# Aq1B_Guppy.net
KiCad netlist of a schematic drawn in Altium Designer
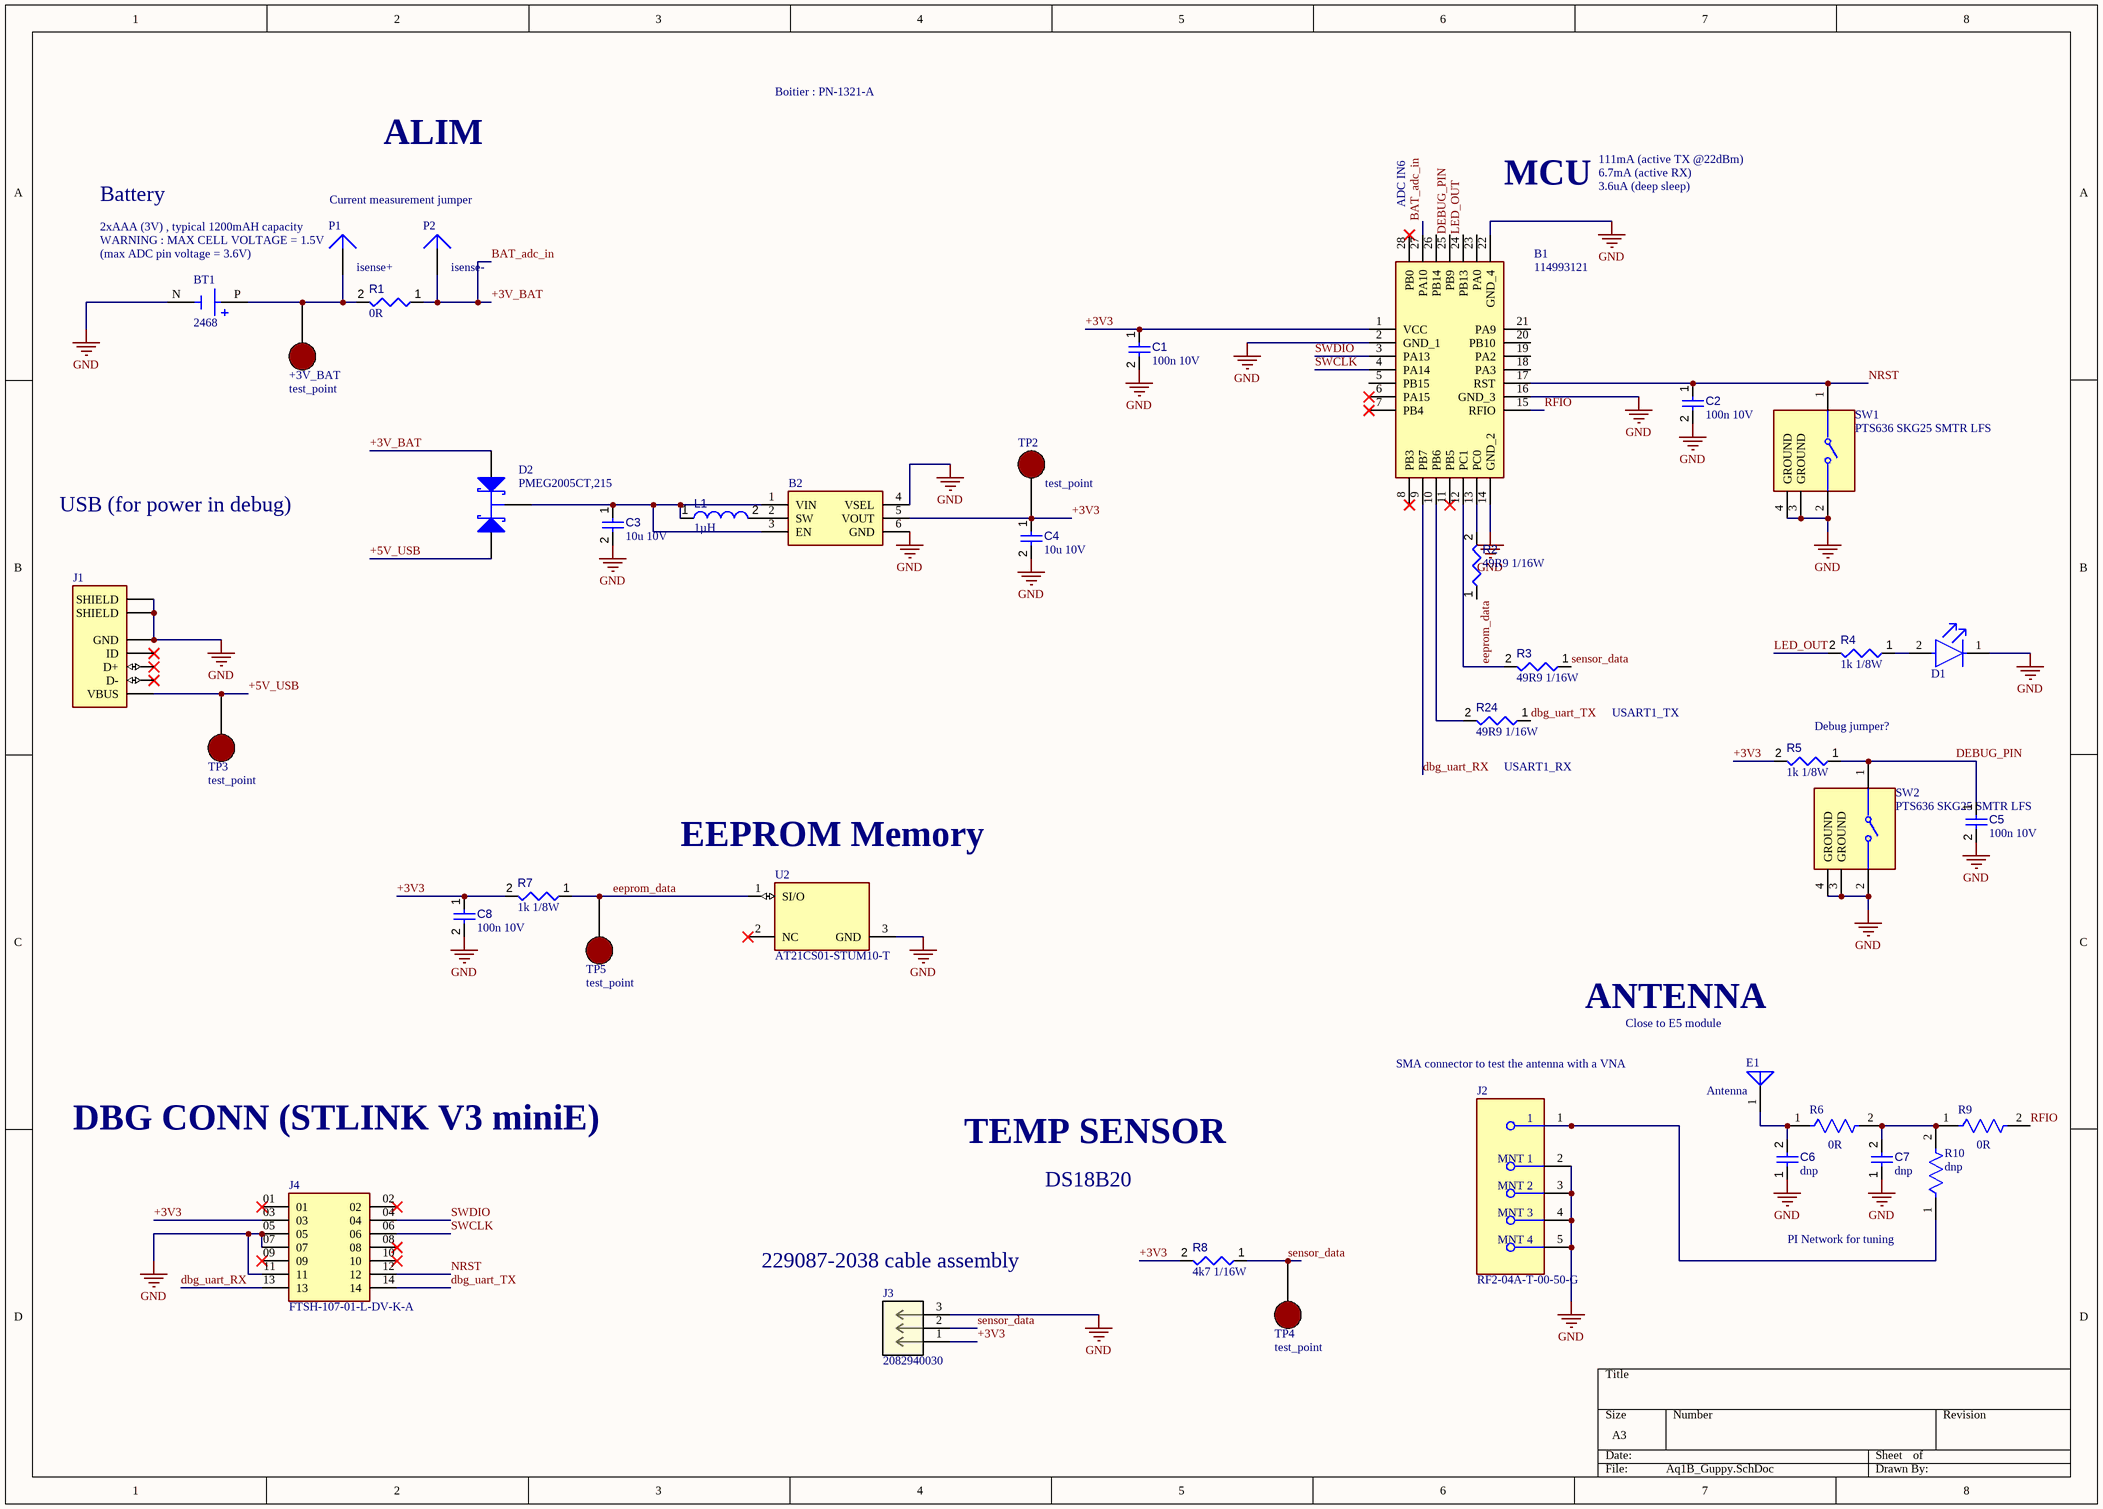
[diagram p0: Aq1B_Guppy.SchDoc]

(export (version "E")
  (design (tool "Eeschema 10.0.6"))
  (components
    (comp (ref "+3V_BAT")
      (value "test_point")
      (footprint "test_point")
      (libsource (lib "test_point") (part "test_point"))
    )
    (comp (ref "B1")
      (value "114993121")
      (footprint "114993121")
      (description "General ISM < 1GHz LoRaWAN Transceiver Module 868MHz, 915MHz Antenna Not Included Surface Mount")
      (fields (field (name "MOUSER PART NUMBER") "713-114993121"))
      (libsource (lib "LoraE5") (part "114993121"))
    )
    (comp (ref "B2")
      (value "~")
      (footprint "SOTFL50P160X60-6N")
      (fields
        (field (name "MOUSER PART NUMBER") "595-TPS61299DRLR")
        (field (name "MANUFACTURER_PART_NUMBER") "TPS61299DRLR")
      )
      (libsource (lib "AqOST_Guppy") (part "TPS61299DRLR"))
    )
    (comp (ref "BT1")
      (value "2468")
      (footprint "BAT_2468")
      (description "Battery Holder, THM, 2 Cell, Cell Size AAA, Plastic ¦ Keystone Electronics 2468")
      (fields (field (name "MF") "Keystone Electronics"))
      (libsource (lib "2468") (part "2468"))
    )
    (comp (ref "C1")
      (value "100n 10V")
      (footprint "CAPC0805(2012)145_L")
      (description "Chip Capacitor, 4.7µF +/-40%, 25V, 0805, Thickness 1.45 mm")
      (fields (field (name "TOLERANCE") "20%") (field (name "Comment") "Capacitor 4.7µF +/-40% 25V 0805"))
      (libsource (lib "Samuel Grall") (part "CAP-NP-2"))
    )
    (comp (ref "C2")
      (value "100n 10V")
      (footprint "CAPC0805(2012)145_L")
      (description "Chip Capacitor, 4.7µF +/-40%, 25V, 0805, Thickness 1.45 mm")
      (fields (field (name "TOLERANCE") "20%") (field (name "Comment") "Capacitor 4.7µF +/-40% 25V 0805"))
      (libsource (lib "Samuel Grall") (part "CAP-NP-2"))
    )
    (comp (ref "C3")
      (value "10u 10V")
      (footprint "CAPC0805(2012)145_L")
      (description "Chip Capacitor, 4.7µF +/-40%, 25V, 0805, Thickness 1.45 mm")
      (fields (field (name "TOLERANCE") "20%") (field (name "Comment") "Capacitor 4.7µF +/-40% 25V 0805"))
      (libsource (lib "Samuel Grall") (part "CAP-NP-2"))
    )
    (comp (ref "C4")
      (value "10u 10V")
      (footprint "CAPC0805(2012)145_L")
      (description "Chip Capacitor, 4.7µF +/-40%, 25V, 0805, Thickness 1.45 mm")
      (fields (field (name "TOLERANCE") "20%") (field (name "Comment") "Capacitor 4.7µF +/-40% 25V 0805"))
      (libsource (lib "Samuel Grall") (part "CAP-NP-2"))
    )
    (comp (ref "C5")
      (value "100n 10V")
      (footprint "CAPC0805(2012)145_L")
      (description "Chip Capacitor, 4.7µF +/-40%, 25V, 0805, Thickness 1.45 mm")
      (fields (field (name "TOLERANCE") "20%") (field (name "Comment") "Capacitor 4.7µF +/-40% 25V 0805"))
      (libsource (lib "Samuel Grall") (part "CAP-NP-2"))
    )
    (comp (ref "C6")
      (value "dnp")
      (footprint "CAPC1608X90X40NL10T20")
      (description "Chip Capacitor, 100 nF, +/- 10%, 50 V, 0603 (1608 Metric)")
      (fields (field (name "TOLERANCE") "10%") (field (name "Comment") "Capacitor 100 nF +/-10% 50 V 0603"))
      (libsource (lib "Samuel Grall") (part "CAP-NP-2"))
    )
    (comp (ref "C7")
      (value "dnp")
      (footprint "CAPC1608X90X40NL10T20")
      (description "Chip Capacitor, 100 nF, +/- 10%, 50 V, 0603 (1608 Metric)")
      (fields (field (name "TOLERANCE") "10%") (field (name "Comment") "Capacitor 100 nF +/-10% 50 V 0603"))
      (libsource (lib "Samuel Grall") (part "CAP-NP-2"))
    )
    (comp (ref "C8")
      (value "100n 10V")
      (footprint "CAPC0805(2012)145_L")
      (description "Chip Capacitor, 4.7µF +/-40%, 25V, 0805, Thickness 1.45 mm")
      (fields (field (name "TOLERANCE") "20%") (field (name "Comment") "Capacitor 4.7µF +/-40% 25V 0805"))
      (libsource (lib "Samuel Grall") (part "CAP-NP-2"))
    )
    (comp (ref "D1")
      (value "SML-D12V8WT86C")
      (footprint "FP-SML-D12-MFG")
      (description "LED RED 1608 SMD")
      (libsource (lib "Altium Content Vault") (part "8706943c75ba83719d021d2fdc84c58"))
    )
    (comp (ref "D2")
      (value "PMEG2005CT,215")
      (footprint "STM-BAT54CFILM-3_V")
      (description "Small Signal Schottky Diode, 40 V, -40 to 150 degC, 3-Pin SOT23, RoHS, Tape and Reel")
      (fields (field (name "MANUFACTURER") "STMicroelectronics"))
      (libsource (lib "Altium Content Vault") (part "DSKY-AAK-3"))
    )
    (comp (ref "E1")
      (value "Antenna")
      (footprint "Antenna")
      (description "Generic Antenna")
      (fields (field (name "PUBLISHER") "Altium Limited"))
      (libsource (lib "Miscellaneous Devices") (part "Antenna"))
    )
    (comp (ref "J1")
      (value "~")
      (footprint "GCT_USB3130-XX-X_REVD")
      (description "USB - micro B USB 2.0 Receptacle Connector 5 Position Through Hole")
      (fields (field (name "MP") "USB3130-30-A") (field (name "MF") "Global Connector Technology"))
      (libsource (lib "AqOST_Guppy") (part "USB3130-XX-X_REVD"))
    )
    (comp (ref "J2")
      (value "RF2-04A-T-00-50-G")
      (footprint "FP-RF2-04A-T-00-50-G-MFG")
      (description "CONN SMA JACK STR 50 OHM PCB")
      (libsource (lib "Altium Content Vault") (part "c65b8a639cdaef1819ea20b5466f8fa"))
    )
    (comp (ref "J3")
      (value "2082940030")
      (footprint "CONN_2082940000-SD_03_MOL")
      (description "Pico-EZmate HC PCB Header, 1.80mm Pitch, Single Row, Gold (Au) Plating, 3 Circuits")
      (fields (field (name "COPYRIGHT") "Copyright (C) 2025 Ultra Librarian. All rights reserved."))
      (libsource (lib "2082940030") (part "2082940030"))
    )
    (comp (ref "J4")
      (value "FTSH-107-01-L-DV-K-A")
      (footprint "SAMTEC_FTSH-107-01-L-DV-K-A")
      (description "Connector Header Surface Mount 14 position 0.050 (1.27mm)")
      (fields (field (name "MF") "Samtec Inc."))
      (libsource (lib "FTSH-107-01-L-DV-K-A") (part "FTSH-107-01-L-DV-K-A"))
    )
    (comp (ref "L1")
      (value "1µH")
      (footprint "INDC2520X120X60NL20T20")
      (description "Chip Inductor, 1 uH, +/- 20%, 1 MHz, -55 to 125 degC, 1008 (2520 Metric), RoHS, Tape and Reel")
      (fields (field (name "TOLERANCE") "20%") (field (name "MANUFACTURER") "Murata"))
      (libsource (lib "Samuel Grall") (part "IND-2"))
    )
    (comp (ref "P1")
      (value "isense+")
      (footprint "PIN1")
      (description "Plug")
      (fields (field (name "PUBLISHER") "Altium Limited"))
      (libsource (lib "Miscellaneous Connectors") (part "Plug"))
    )
    (comp (ref "P2")
      (value "isense-")
      (footprint "PIN1")
      (description "Plug")
      (fields (field (name "PUBLISHER") "Altium Limited"))
      (libsource (lib "Miscellaneous Connectors") (part "Plug"))
    )
    (comp (ref "R1")
      (value "0R")
      (footprint "RESC0805(2012)_L")
      (description "Chip Resistor, 470 Ohms, +/-5%, 125 mW, -55 to 155 degC, 0805")
      (fields (field (name "TOLERANCE") "5%") (field (name "POWER") "125mW"))
      (libsource (lib "Samuel Grall") (part "RES-2"))
    )
    (comp (ref "R2")
      (value "49R9 1/16W")
      (footprint "RESC0805(2012)_L")
      (description "Chip Resistor, 470 Ohms, +/-5%, 125 mW, -55 to 155 degC, 0805")
      (fields (field (name "TOLERANCE") "5%") (field (name "POWER") "125mW"))
      (libsource (lib "Samuel Grall") (part "RES-2"))
    )
    (comp (ref "R3")
      (value "49R9 1/16W")
      (footprint "RESC0805(2012)_L")
      (description "Chip Resistor, 470 Ohms, +/-5%, 125 mW, -55 to 155 degC, 0805")
      (fields (field (name "TOLERANCE") "5%") (field (name "POWER") "125mW"))
      (libsource (lib "Samuel Grall") (part "RES-2"))
    )
    (comp (ref "R4")
      (value "1k 1/8W")
      (footprint "RESC0805(2012)_L")
      (description "Chip Resistor, 470 Ohms, +/-5%, 125 mW, -55 to 155 degC, 0805")
      (fields (field (name "TOLERANCE") "5%") (field (name "POWER") "125mW"))
      (libsource (lib "Samuel Grall") (part "RES-2"))
    )
    (comp (ref "R5")
      (value "1k 1/8W")
      (footprint "RESC0805(2012)_L")
      (description "Chip Resistor, 470 Ohms, +/-5%, 125 mW, -55 to 155 degC, 0805")
      (fields (field (name "TOLERANCE") "5%") (field (name "POWER") "125mW"))
      (libsource (lib "Samuel Grall") (part "RES-2"))
    )
    (comp (ref "R6")
      (value "0R")
      (footprint "FP-MCT0603-IPC_B")
      (description "RES SMD 100 OHM 1% 1/8W 0603")
      (fields (field (name "TOLERANCE") "0.5%"))
      (libsource (lib "Altium Content Vault") (part "1029c3af85768c4190bb7ad29bc67b5"))
    )
    (comp (ref "R7")
      (value "1k 1/8W")
      (footprint "RESC0805(2012)_L")
      (description "Chip Resistor, 470 Ohms, +/-5%, 125 mW, -55 to 155 degC, 0805")
      (fields (field (name "TOLERANCE") "5%") (field (name "POWER") "125mW"))
      (libsource (lib "Samuel Grall") (part "RES-2"))
    )
    (comp (ref "R8")
      (value "4k7 1/16W")
      (footprint "RESC0805(2012)_L")
      (description "Chip Resistor, 470 Ohms, +/-5%, 125 mW, -55 to 155 degC, 0805")
      (fields (field (name "TOLERANCE") "5%") (field (name "POWER") "125mW"))
      (libsource (lib "Samuel Grall") (part "RES-2"))
    )
    (comp (ref "R9")
      (value "0R")
      (footprint "FP-MCT0603-IPC_B")
      (description "RES SMD 100 OHM 1% 1/8W 0603")
      (fields (field (name "TOLERANCE") "0.5%"))
      (libsource (lib "Altium Content Vault") (part "1029c3af85768c4190bb7ad29bc67b5"))
    )
    (comp (ref "R10")
      (value "dnp")
      (footprint "FP-MCT0603-IPC_B")
      (description "RES SMD 100 OHM 1% 1/8W 0603")
      (fields (field (name "TOLERANCE") "0.5%"))
      (libsource (lib "Altium Content Vault") (part "1029c3af85768c4190bb7ad29bc67b5"))
    )
    (comp (ref "R24")
      (value "49R9 1/16W")
      (footprint "RESC0805(2012)_L")
      (description "Chip Resistor, 470 Ohms, +/-5%, 125 mW, -55 to 155 degC, 0805")
      (fields (field (name "TOLERANCE") "5%") (field (name "POWER") "125mW"))
      (libsource (lib "Samuel Grall") (part "RES-2"))
    )
    (comp (ref "SW1")
      (value "PTS636 SKG25 SMTR LFS")
      (footprint "FP-PTS636_SKG25_SMTR_LFS-MFG")
      (description "TACT 6.0 X 3.5, 2.5 MM H, 250GF,")
      (libsource (lib "Altium Content Vault") (part "bdfe703aeb3461bf7c331fe9d798369"))
    )
    (comp (ref "SW2")
      (value "PTS636 SKG25 SMTR LFS")
      (footprint "FP-PTS636_SKG25_SMTR_LFS-MFG")
      (description "TACT 6.0 X 3.5, 2.5 MM H, 250GF,")
      (libsource (lib "Altium Content Vault") (part "bdfe703aeb3461bf7c331fe9d798369"))
    )
    (comp (ref "TP2")
      (value "test_point")
      (footprint "test_point")
      (libsource (lib "test_point") (part "test_point"))
    )
    (comp (ref "TP3")
      (value "test_point")
      (footprint "test_point")
      (libsource (lib "test_point") (part "test_point"))
    )
    (comp (ref "TP4")
      (value "test_point")
      (footprint "test_point")
      (libsource (lib "test_point") (part "test_point"))
    )
    (comp (ref "TP5")
      (value "test_point")
      (footprint "test_point")
      (libsource (lib "test_point") (part "test_point"))
    )
    (comp (ref "U2")
      (value "AT21CS01-STUM10-T")
      (footprint "FP-3TS1-IPC_C")
      (description "IC EEPROM 1K I2C 125KHZ SOT23")
      (fields
        (field (name "OCTOPART") "https://octopart.com/at21cs01-stum10-t-microchip-77757908")
        (field (name "MANUFACTURER") "Microchip")
      )
      (libsource (lib "Altium Content Vault") (part "0a6dd273ebc354a2180ac5f4cab3358"))
    )
  )
  (nets
    (net (code "1") (name "/+3V3") (class "Default")
      (node (ref "B1") (pin "1") (pinfunction "VCC_1") (pintype "passive"))
      (node (ref "B2") (pin "5") (pinfunction "VOUT_5") (pintype "passive"))
      (node (ref "C1") (pin "1") (pinfunction "1_1") (pintype "passive"))
      (node (ref "C4") (pin "1") (pinfunction "1_1") (pintype "passive"))
      (node (ref "C8") (pin "1") (pinfunction "1_1") (pintype "passive"))
      (node (ref "J3") (pin "1") (pinfunction "1_1") (pintype "passive"))
      (node (ref "J4") (pin "03") (pinfunction "03_03") (pintype "passive"))
      (node (ref "R5") (pin "2") (pinfunction "2_2") (pintype "passive"))
      (node (ref "R7") (pin "2") (pinfunction "2_2") (pintype "passive"))
      (node (ref "R8") (pin "2") (pinfunction "2_2") (pintype "passive"))
      (node (ref "TP2") (pin "0") (pinfunction "0_0") (pintype "passive"))
    )
    (net (code "2") (name "/+3V_BAT") (class "Default")
      (node (ref "B1") (pin "27") (pinfunction "PA10_27") (pintype "passive"))
      (node (ref "D2") (pin "1") (pinfunction "A_1") (pintype "passive"))
      (node (ref "P2") (pin "1") (pinfunction "1_1") (pintype "passive"))
      (node (ref "R1") (pin "1") (pinfunction "1_1") (pintype "passive"))
    )
    (net (code "3") (name "/+5V_USB") (class "Default")
      (node (ref "D2") (pin "2") (pinfunction "A_2") (pintype "passive"))
      (node (ref "J1") (pin "1") (pinfunction "VBUS_1") (pintype "power_in"))
      (node (ref "TP3") (pin "0") (pinfunction "0_0") (pintype "passive"))
    )
    (net (code "4") (name "/DEBUG_PIN") (class "Default")
      (node (ref "B1") (pin "25") (pinfunction "PB9_25") (pintype "passive"))
      (node (ref "C5") (pin "1") (pinfunction "1_1") (pintype "passive"))
      (node (ref "R5") (pin "1") (pinfunction "1_1") (pintype "passive"))
      (node (ref "SW2") (pin "1") (pinfunction "1_1") (pintype "passive"))
    )
    (net (code "5") (name "/LED_OUT") (class "Default")
      (node (ref "B1") (pin "24") (pinfunction "PB13_24") (pintype "passive"))
      (node (ref "R4") (pin "2") (pinfunction "2_2") (pintype "passive"))
    )
    (net (code "6") (name "/NRST") (class "Default")
      (node (ref "B1") (pin "17") (pinfunction "RST_17") (pintype "passive"))
      (node (ref "C2") (pin "1") (pinfunction "1_1") (pintype "passive"))
      (node (ref "J4") (pin "12") (pinfunction "12_12") (pintype "passive"))
      (node (ref "SW1") (pin "1") (pinfunction "1_1") (pintype "passive"))
    )
    (net (code "7") (name "/RFIO") (class "Default")
      (node (ref "B1") (pin "15") (pinfunction "RFIO_15") (pintype "passive"))
      (node (ref "R9") (pin "2") (pinfunction "2_2") (pintype "passive"))
    )
    (net (code "8") (name "/SWCLK") (class "Default")
      (node (ref "B1") (pin "4") (pinfunction "PA14_4") (pintype "passive"))
      (node (ref "J4") (pin "06") (pinfunction "06_06") (pintype "passive"))
    )
    (net (code "9") (name "/SWDIO") (class "Default")
      (node (ref "B1") (pin "3") (pinfunction "PA13_3") (pintype "passive"))
      (node (ref "J4") (pin "04") (pinfunction "04_04") (pintype "passive"))
    )
    (net (code "10") (name "/dbg_uart_RX") (class "Default")
      (node (ref "B1") (pin "9") (pinfunction "PB7_9") (pintype "passive"))
      (node (ref "J4") (pin "13") (pinfunction "13_13") (pintype "passive"))
    )
    (net (code "11") (name "/dbg_uart_TX") (class "Default")
      (node (ref "J4") (pin "14") (pinfunction "14_14") (pintype "passive"))
      (node (ref "R24") (pin "1") (pinfunction "1_1") (pintype "passive"))
    )
    (net (code "12") (name "/eeprom_data") (class "Default")
      (node (ref "R2") (pin "1") (pinfunction "1_1") (pintype "passive"))
      (node (ref "R7") (pin "1") (pinfunction "1_1") (pintype "passive"))
      (node (ref "TP5") (pin "0") (pinfunction "0_0") (pintype "passive"))
      (node (ref "U2") (pin "1") (pinfunction "SI/O_1") (pintype "bidirectional"))
    )
    (net (code "13") (name "/sensor_data") (class "Default")
      (node (ref "J3") (pin "2") (pinfunction "2_2") (pintype "passive"))
      (node (ref "R3") (pin "1") (pinfunction "1_1") (pintype "passive"))
      (node (ref "R8") (pin "1") (pinfunction "1_1") (pintype "passive"))
      (node (ref "TP4") (pin "0") (pinfunction "0_0") (pintype "passive"))
    )
    (net (code "14") (name "GND") (class "Default")
      (node (ref "B1") (pin "14") (pinfunction "GND_2_14") (pintype "passive"))
      (node (ref "B1") (pin "16") (pinfunction "GND_3_16") (pintype "passive"))
      (node (ref "B1") (pin "2") (pinfunction "GND_1_2") (pintype "passive"))
      (node (ref "B1") (pin "22") (pinfunction "GND_4_22") (pintype "passive"))
      (node (ref "B2") (pin "4") (pinfunction "VSEL_4") (pintype "passive"))
      (node (ref "B2") (pin "6") (pinfunction "GND_6") (pintype "passive"))
      (node (ref "BT1") (pin "N") (pinfunction "NEG_N") (pintype "passive"))
      (node (ref "C1") (pin "2") (pinfunction "2_2") (pintype "passive"))
      (node (ref "C2") (pin "2") (pinfunction "2_2") (pintype "passive"))
      (node (ref "C3") (pin "2") (pinfunction "2_2") (pintype "passive"))
      (node (ref "C4") (pin "2") (pinfunction "2_2") (pintype "passive"))
      (node (ref "C5") (pin "2") (pinfunction "2_2") (pintype "passive"))
      (node (ref "C6") (pin "1") (pinfunction "1_1") (pintype "passive"))
      (node (ref "C7") (pin "1") (pinfunction "1_1") (pintype "passive"))
      (node (ref "C8") (pin "2") (pinfunction "2_2") (pintype "passive"))
      (node (ref "D1") (pin "1") (pinfunction "C_1") (pintype "passive"))
      (node (ref "J1") (pin "5") (pinfunction "GND_5") (pintype "power_in"))
      (node (ref "J1") (pin "6") (pinfunction "SHIELD_6") (pintype "passive"))
      (node (ref "J1") (pin "7") (pinfunction "SHIELD_7") (pintype "passive"))
      (node (ref "J2") (pin "2") (pinfunction "MNT_1_2") (pintype "passive"))
      (node (ref "J2") (pin "3") (pinfunction "MNT_2_3") (pintype "passive"))
      (node (ref "J2") (pin "4") (pinfunction "MNT_3_4") (pintype "passive"))
      (node (ref "J2") (pin "5") (pinfunction "MNT_4_5") (pintype "passive"))
      (node (ref "J3") (pin "3") (pinfunction "3_3") (pintype "passive"))
      (node (ref "J4") (pin "05") (pinfunction "05_05") (pintype "passive"))
      (node (ref "J4") (pin "07") (pinfunction "07_07") (pintype "passive"))
      (node (ref "J4") (pin "11") (pinfunction "11_11") (pintype "passive"))
      (node (ref "SW1") (pin "2") (pinfunction "2_2") (pintype "passive"))
      (node (ref "SW1") (pin "3") (pinfunction "GROUND_3") (pintype "power_in"))
      (node (ref "SW1") (pin "4") (pinfunction "GROUND_4") (pintype "power_in"))
      (node (ref "SW2") (pin "2") (pinfunction "2_2") (pintype "passive"))
      (node (ref "SW2") (pin "3") (pinfunction "GROUND_3") (pintype "power_in"))
      (node (ref "SW2") (pin "4") (pinfunction "GROUND_4") (pintype "power_in"))
      (node (ref "U2") (pin "3") (pinfunction "GND_3") (pintype "power_in"))
    )
    (net (code "15") (name "Net-(B1-PB6)") (class "Default")
      (node (ref "B1") (pin "10") (pinfunction "PB6_10") (pintype "passive"))
      (node (ref "R24") (pin "2") (pinfunction "2_2") (pintype "passive"))
    )
    (net (code "16") (name "Net-(B1-PC0)") (class "Default")
      (node (ref "B1") (pin "13") (pinfunction "PC0_13") (pintype "passive"))
      (node (ref "R2") (pin "2") (pinfunction "2_2") (pintype "passive"))
    )
    (net (code "17") (name "Net-(B1-PC1)") (class "Default")
      (node (ref "B1") (pin "12") (pinfunction "PC1_12") (pintype "passive"))
      (node (ref "R3") (pin "2") (pinfunction "2_2") (pintype "passive"))
    )
    (net (code "18") (name "Net-(B2-EN)") (class "Default")
      (node (ref "B2") (pin "1") (pinfunction "VIN_1") (pintype "passive"))
      (node (ref "B2") (pin "3") (pinfunction "EN_3") (pintype "passive"))
      (node (ref "C3") (pin "1") (pinfunction "1_1") (pintype "passive"))
      (node (ref "D2") (pin "3") (pinfunction "K_3") (pintype "passive"))
      (node (ref "L1") (pin "1") (pinfunction "1_1") (pintype "passive"))
    )
    (net (code "19") (name "Net-(B2-SW)") (class "Default")
      (node (ref "B2") (pin "2") (pinfunction "SW_2") (pintype "passive"))
      (node (ref "L1") (pin "2") (pinfunction "2_2") (pintype "passive"))
    )
    (net (code "20") (name "Net-(BT1-POS)") (class "Default")
      (node (ref "+3V_BAT") (pin "0") (pinfunction "0_0") (pintype "passive"))
      (node (ref "BT1") (pin "P") (pinfunction "POS_P") (pintype "passive"))
      (node (ref "P1") (pin "1") (pinfunction "1_1") (pintype "passive"))
      (node (ref "R1") (pin "2") (pinfunction "2_2") (pintype "passive"))
    )
    (net (code "21") (name "Net-(C7-Pad2)") (class "Default")
      (node (ref "C7") (pin "2") (pinfunction "2_2") (pintype "passive"))
      (node (ref "R10") (pin "2") (pinfunction "2_2") (pintype "passive"))
      (node (ref "R6") (pin "2") (pinfunction "2_2") (pintype "passive"))
      (node (ref "R9") (pin "1") (pinfunction "1_1") (pintype "passive"))
    )
    (net (code "22") (name "Net-(D1-A)") (class "Default")
      (node (ref "D1") (pin "2") (pinfunction "A_2") (pintype "passive"))
      (node (ref "R4") (pin "1") (pinfunction "1_1") (pintype "passive"))
    )
    (net (code "23") (name "Net-(E1-A)") (class "Default")
      (node (ref "C6") (pin "2") (pinfunction "2_2") (pintype "passive"))
      (node (ref "E1") (pin "1") (pinfunction "A_1") (pintype "passive"))
      (node (ref "R6") (pin "1") (pinfunction "1_1") (pintype "passive"))
    )
    (net (code "24") (name "Net-(J2-Pad1)") (class "Default")
      (node (ref "J2") (pin "1") (pinfunction "1_1") (pintype "passive"))
      (node (ref "R10") (pin "1") (pinfunction "1_1") (pintype "passive"))
    )
    (net (code "25") (name "unconnected-(B1-PA0-Pad23)") (class "Default")
      (node (ref "B1") (pin "23") (pinfunction "PA0_23") (pintype "passive"))
    )
    (net (code "26") (name "unconnected-(B1-PA2-Pad19)") (class "Default")
      (node (ref "B1") (pin "19") (pinfunction "PA2_19") (pintype "passive"))
    )
    (net (code "27") (name "unconnected-(B1-PA3-Pad18)") (class "Default")
      (node (ref "B1") (pin "18") (pinfunction "PA3_18") (pintype "passive"))
    )
    (net (code "28") (name "unconnected-(B1-PA9-Pad21)") (class "Default")
      (node (ref "B1") (pin "21") (pinfunction "PA9_21") (pintype "passive"))
    )
    (net (code "29") (name "unconnected-(B1-PA15-Pad6)") (class "Default")
      (node (ref "B1") (pin "6") (pinfunction "PA15_6") (pintype "passive+no_connect"))
    )
    (net (code "30") (name "unconnected-(B1-PB0-Pad28)") (class "Default")
      (node (ref "B1") (pin "28") (pinfunction "PB0_28") (pintype "passive+no_connect"))
    )
    (net (code "31") (name "unconnected-(B1-PB3-Pad8)") (class "Default")
      (node (ref "B1") (pin "8") (pinfunction "PB3_8") (pintype "passive+no_connect"))
    )
    (net (code "32") (name "unconnected-(B1-PB4-Pad7)") (class "Default")
      (node (ref "B1") (pin "7") (pinfunction "PB4_7") (pintype "passive+no_connect"))
    )
    (net (code "33") (name "unconnected-(B1-PB5-Pad11)") (class "Default")
      (node (ref "B1") (pin "11") (pinfunction "PB5_11") (pintype "passive+no_connect"))
    )
    (net (code "34") (name "unconnected-(B1-PB10-Pad20)") (class "Default")
      (node (ref "B1") (pin "20") (pinfunction "PB10_20") (pintype "passive"))
    )
    (net (code "35") (name "unconnected-(B1-PB14-Pad26)") (class "Default")
      (node (ref "B1") (pin "26") (pinfunction "PB14_26") (pintype "passive"))
    )
    (net (code "36") (name "unconnected-(B1-PB15-Pad5)") (class "Default")
      (node (ref "B1") (pin "5") (pinfunction "PB15_5") (pintype "passive"))
    )
    (net (code "37") (name "unconnected-(J1-D+-Pad3)") (class "Default")
      (node (ref "J1") (pin "3") (pinfunction "D+_3") (pintype "bidirectional+no_connect"))
    )
    (net (code "38") (name "unconnected-(J1-D--Pad2)") (class "Default")
      (node (ref "J1") (pin "2") (pinfunction "D-_2") (pintype "bidirectional+no_connect"))
    )
    (net (code "39") (name "unconnected-(J1-ID-Pad4)") (class "Default")
      (node (ref "J1") (pin "4") (pinfunction "ID_4") (pintype "passive+no_connect"))
    )
    (net (code "40") (name "unconnected-(J4-Pad01)") (class "Default")
      (node (ref "J4") (pin "01") (pinfunction "01_01") (pintype "passive+no_connect"))
    )
    (net (code "41") (name "unconnected-(J4-Pad02)") (class "Default")
      (node (ref "J4") (pin "02") (pinfunction "02_02") (pintype "passive+no_connect"))
    )
    (net (code "42") (name "unconnected-(J4-Pad08)") (class "Default")
      (node (ref "J4") (pin "08") (pinfunction "08_08") (pintype "passive+no_connect"))
    )
    (net (code "43") (name "unconnected-(J4-Pad09)") (class "Default")
      (node (ref "J4") (pin "09") (pinfunction "09_09") (pintype "passive+no_connect"))
    )
    (net (code "44") (name "unconnected-(J4-Pad10)") (class "Default")
      (node (ref "J4") (pin "10") (pinfunction "10_10") (pintype "passive+no_connect"))
    )
    (net (code "45") (name "unconnected-(U2-NC-Pad2)") (class "Default")
      (node (ref "U2") (pin "2") (pinfunction "NC_2") (pintype "passive+no_connect"))
    )
  )
)
